# PT8211_T3_0_2.net
KiCad netlist of a schematic drawn in EAGLE
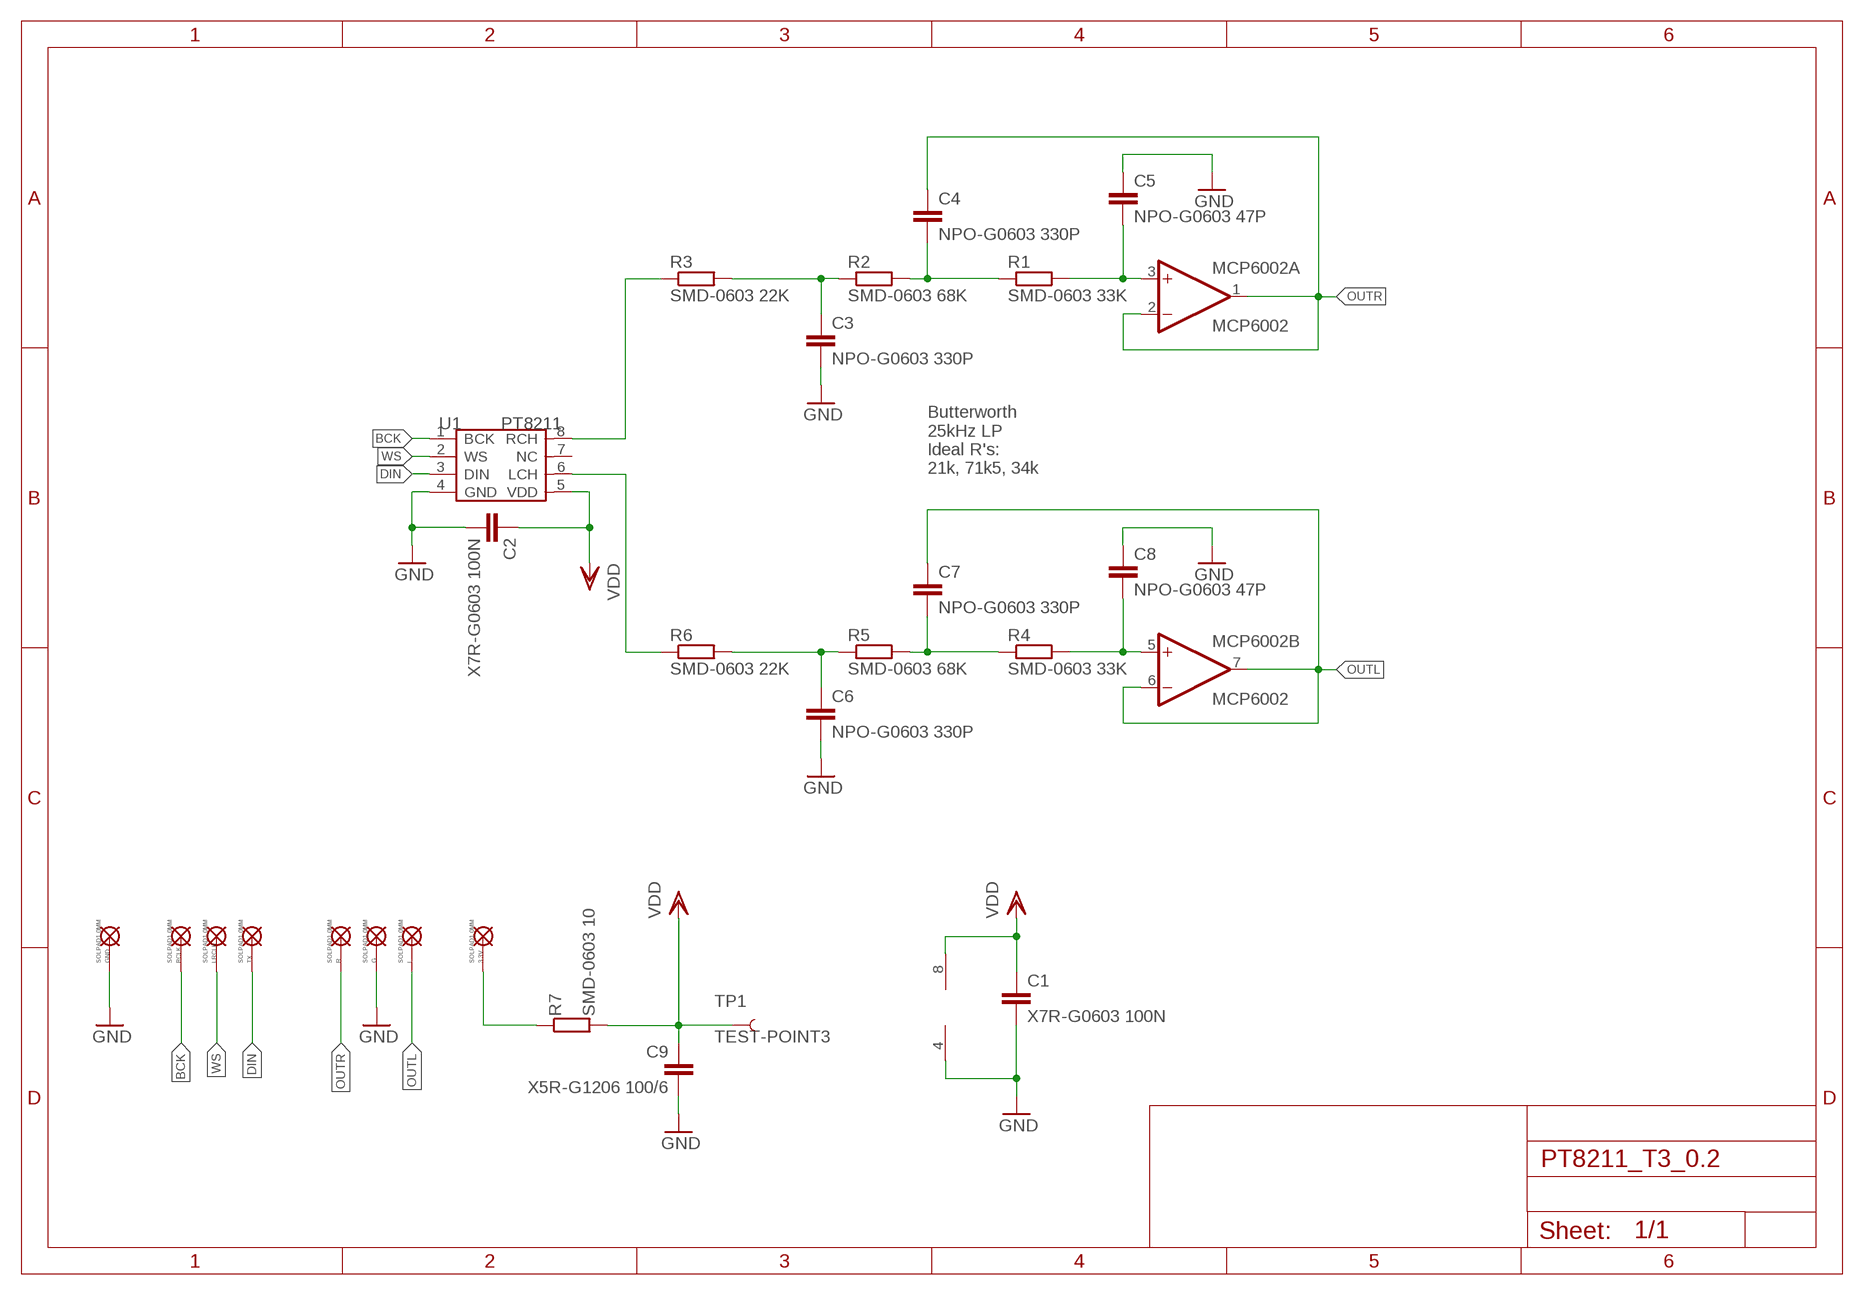
[diagram p0: schematic, sheet 1]

(export (version "E")
  (design (tool "Eeschema 10.0.6"))
  (components
    (comp (ref "3.3V")
      (value "SOLPAD1,0MM")
      (footprint "eagle-import:SOLPAD1MM")
      (libsource (lib "eagle-import") (part "SOLPAD1,0MM"))
    )
    (comp (ref "BCLK")
      (value "SOLPAD1,0MM")
      (footprint "eagle-import:SOLPAD1MM")
      (libsource (lib "eagle-import") (part "SOLPAD1,0MM"))
    )
    (comp (ref "C1")
      (value "X7R-G0603 100N")
      (footprint "eagle-import:C0603K")
      (libsource (lib "eagle-import") (part "C-EUC0603K"))
    )
    (comp (ref "C2")
      (value "X7R-G0603 100N")
      (footprint "eagle-import:C0603K")
      (libsource (lib "eagle-import") (part "C-EUC0603K"))
    )
    (comp (ref "C3")
      (value "NPO-G0603 330P")
      (footprint "eagle-import:C0603K")
      (libsource (lib "eagle-import") (part "C-EUC0603K"))
    )
    (comp (ref "C4")
      (value "NPO-G0603 330P")
      (footprint "eagle-import:C0603K")
      (libsource (lib "eagle-import") (part "C-EUC0603K"))
    )
    (comp (ref "C5")
      (value "NPO-G0603 47P")
      (footprint "eagle-import:C0603K")
      (libsource (lib "eagle-import") (part "C-EUC0603K"))
    )
    (comp (ref "C6")
      (value "NPO-G0603 330P")
      (footprint "eagle-import:C0603K")
      (libsource (lib "eagle-import") (part "C-EUC0603K"))
    )
    (comp (ref "C7")
      (value "NPO-G0603 330P")
      (footprint "eagle-import:C0603K")
      (libsource (lib "eagle-import") (part "C-EUC0603K"))
    )
    (comp (ref "C8")
      (value "NPO-G0603 47P")
      (footprint "eagle-import:C0603K")
      (libsource (lib "eagle-import") (part "C-EUC0603K"))
    )
    (comp (ref "C9")
      (value "X5R-G1206 100/6")
      (footprint "eagle-import:C1206K")
      (libsource (lib "eagle-import") (part "C-EUC1206K"))
    )
    (comp (ref "G")
      (value "SOLPAD1,0MM")
      (footprint "eagle-import:SOLPAD1MM")
      (libsource (lib "eagle-import") (part "SOLPAD1,0MM"))
    )
    (comp (ref "GND")
      (value "SOLPAD1,0MM")
      (footprint "eagle-import:SOLPAD1MM")
      (libsource (lib "eagle-import") (part "SOLPAD1,0MM"))
    )
    (comp (ref "L")
      (value "SOLPAD1,0MM")
      (footprint "eagle-import:SOLPAD1MM")
      (libsource (lib "eagle-import") (part "SOLPAD1,0MM"))
    )
    (comp (ref "LRCLK")
      (value "SOLPAD1,0MM")
      (footprint "eagle-import:SOLPAD1MM")
      (libsource (lib "eagle-import") (part "SOLPAD1,0MM"))
    )
    (comp (ref "MCP6002")
      (value "MCP6002")
      (footprint "eagle-import:SO08")
      (libsource (lib "eagle-import") (part "MCP602SN"))
    )
    (comp (ref "R")
      (value "SOLPAD1,0MM")
      (footprint "eagle-import:SOLPAD1MM")
      (libsource (lib "eagle-import") (part "SOLPAD1,0MM"))
    )
    (comp (ref "R1")
      (value "SMD-0603 33K")
      (footprint "eagle-import:R0603")
      (libsource (lib "eagle-import") (part "R-EU_R0603"))
    )
    (comp (ref "R2")
      (value "SMD-0603 68K")
      (footprint "eagle-import:R0603")
      (libsource (lib "eagle-import") (part "R-EU_R0603"))
    )
    (comp (ref "R3")
      (value "SMD-0603 22K")
      (footprint "eagle-import:R0603")
      (libsource (lib "eagle-import") (part "R-EU_R0603"))
    )
    (comp (ref "R4")
      (value "SMD-0603 33K")
      (footprint "eagle-import:R0603")
      (libsource (lib "eagle-import") (part "R-EU_R0603"))
    )
    (comp (ref "R5")
      (value "SMD-0603 68K")
      (footprint "eagle-import:R0603")
      (libsource (lib "eagle-import") (part "R-EU_R0603"))
    )
    (comp (ref "R6")
      (value "SMD-0603 22K")
      (footprint "eagle-import:R0603")
      (libsource (lib "eagle-import") (part "R-EU_R0603"))
    )
    (comp (ref "R7")
      (value "SMD-0603 10")
      (footprint "eagle-import:R0603")
      (libsource (lib "eagle-import") (part "R-EU_R0603"))
    )
    (comp (ref "TP1")
      (value "TEST-POINT3")
      (footprint "eagle-import:PAD.03X.03")
      (libsource (lib "eagle-import") (part "TEST-POINT3"))
    )
    (comp (ref "TX")
      (value "SOLPAD1,0MM")
      (footprint "eagle-import:SOLPAD1MM")
      (libsource (lib "eagle-import") (part "SOLPAD1,0MM"))
    )
    (comp (ref "U1")
      (value "PT8211")
      (footprint "eagle-import:SOP8-6.0-4.9X3.9")
      (libsource (lib "eagle-import") (part "PT8211-SOP8"))
    )
  )
  (nets
    (net (code "1") (name "BCK") (class "Default")
      (node (ref "BCLK") (pin "P$1") (pinfunction "P$1_P$1") (pintype "bidirectional"))
      (node (ref "U1") (pin "1") (pinfunction "BCK_1") (pintype "input"))
    )
    (net (code "2") (name "DIN") (class "Default")
      (node (ref "TX") (pin "P$1") (pinfunction "P$1_P$1") (pintype "bidirectional"))
      (node (ref "U1") (pin "3") (pinfunction "DIN_3") (pintype "input"))
    )
    (net (code "3") (name "GND") (class "Default")
      (node (ref "C1") (pin "2") (pinfunction "2_2") (pintype "passive"))
      (node (ref "C2") (pin "2") (pinfunction "2_2") (pintype "passive"))
      (node (ref "C3") (pin "2") (pinfunction "2_2") (pintype "passive"))
      (node (ref "C5") (pin "1") (pinfunction "1_1") (pintype "passive"))
      (node (ref "C6") (pin "2") (pinfunction "2_2") (pintype "passive"))
      (node (ref "C8") (pin "1") (pinfunction "1_1") (pintype "passive"))
      (node (ref "C9") (pin "2") (pinfunction "2_2") (pintype "passive"))
      (node (ref "G") (pin "P$1") (pinfunction "P$1_P$1") (pintype "bidirectional"))
      (node (ref "GND") (pin "P$1") (pinfunction "P$1_P$1") (pintype "bidirectional"))
      (node (ref "MCP6002") (pin "4") (pinfunction "V-_4") (pintype "power_in"))
      (node (ref "U1") (pin "4") (pinfunction "GND_4") (pintype "power_in"))
    )
    (net (code "4") (name "Net-(3.3V-PadP$1)") (class "Default")
      (node (ref "3.3V") (pin "P$1") (pinfunction "P$1_P$1") (pintype "bidirectional"))
      (node (ref "R7") (pin "1") (pinfunction "1_1") (pintype "passive"))
    )
    (net (code "5") (name "Net-(C3-Pad1)") (class "Default")
      (node (ref "C3") (pin "1") (pinfunction "1_1") (pintype "passive"))
      (node (ref "R2") (pin "1") (pinfunction "1_1") (pintype "passive"))
      (node (ref "R3") (pin "2") (pinfunction "2_2") (pintype "passive"))
    )
    (net (code "6") (name "Net-(C4-Pad2)") (class "Default")
      (node (ref "C4") (pin "2") (pinfunction "2_2") (pintype "passive"))
      (node (ref "R1") (pin "1") (pinfunction "1_1") (pintype "passive"))
      (node (ref "R2") (pin "2") (pinfunction "2_2") (pintype "passive"))
    )
    (net (code "7") (name "Net-(C6-Pad1)") (class "Default")
      (node (ref "C6") (pin "1") (pinfunction "1_1") (pintype "passive"))
      (node (ref "R5") (pin "1") (pinfunction "1_1") (pintype "passive"))
      (node (ref "R6") (pin "2") (pinfunction "2_2") (pintype "passive"))
    )
    (net (code "8") (name "Net-(C7-Pad2)") (class "Default")
      (node (ref "C7") (pin "2") (pinfunction "2_2") (pintype "passive"))
      (node (ref "R4") (pin "1") (pinfunction "1_1") (pintype "passive"))
      (node (ref "R5") (pin "2") (pinfunction "2_2") (pintype "passive"))
    )
    (net (code "9") (name "Net-(MCP6002A-+IN)") (class "Default")
      (node (ref "C5") (pin "2") (pinfunction "2_2") (pintype "passive"))
      (node (ref "MCP6002") (pin "3") (pinfunction "+IN_3") (pintype "input"))
      (node (ref "R1") (pin "2") (pinfunction "2_2") (pintype "passive"))
    )
    (net (code "10") (name "Net-(MCP6002B-+IN)") (class "Default")
      (node (ref "C8") (pin "2") (pinfunction "2_2") (pintype "passive"))
      (node (ref "MCP6002") (pin "5") (pinfunction "+IN_5") (pintype "input"))
      (node (ref "R4") (pin "2") (pinfunction "2_2") (pintype "passive"))
    )
    (net (code "11") (name "Net-(U1-LCH)") (class "Default")
      (node (ref "R6") (pin "1") (pinfunction "1_1") (pintype "passive"))
      (node (ref "U1") (pin "6") (pinfunction "LCH_6") (pintype "output"))
    )
    (net (code "12") (name "Net-(U1-RCH)") (class "Default")
      (node (ref "R3") (pin "1") (pinfunction "1_1") (pintype "passive"))
      (node (ref "U1") (pin "8") (pinfunction "RCH_8") (pintype "output"))
    )
    (net (code "13") (name "OUTL") (class "Default")
      (node (ref "C7") (pin "1") (pinfunction "1_1") (pintype "passive"))
      (node (ref "L") (pin "P$1") (pinfunction "P$1_P$1") (pintype "bidirectional"))
      (node (ref "MCP6002") (pin "6") (pinfunction "-IN_6") (pintype "input"))
      (node (ref "MCP6002") (pin "7") (pinfunction "OUT_7") (pintype "output"))
    )
    (net (code "14") (name "OUTR") (class "Default")
      (node (ref "C4") (pin "1") (pinfunction "1_1") (pintype "passive"))
      (node (ref "MCP6002") (pin "1") (pinfunction "OUT_1") (pintype "output"))
      (node (ref "MCP6002") (pin "2") (pinfunction "-IN_2") (pintype "input"))
      (node (ref "R") (pin "P$1") (pinfunction "P$1_P$1") (pintype "bidirectional"))
    )
    (net (code "15") (name "VDD") (class "Default")
      (node (ref "C1") (pin "1") (pinfunction "1_1") (pintype "passive"))
      (node (ref "C2") (pin "1") (pinfunction "1_1") (pintype "passive"))
      (node (ref "C9") (pin "1") (pinfunction "1_1") (pintype "passive"))
      (node (ref "MCP6002") (pin "8") (pinfunction "V+_8") (pintype "power_in"))
      (node (ref "R7") (pin "2") (pinfunction "2_2") (pintype "passive"))
      (node (ref "TP1") (pin "P$1") (pinfunction "1_P$1") (pintype "bidirectional"))
      (node (ref "U1") (pin "5") (pinfunction "VDD_5") (pintype "power_in"))
    )
    (net (code "16") (name "WS") (class "Default")
      (node (ref "LRCLK") (pin "P$1") (pinfunction "P$1_P$1") (pintype "bidirectional"))
      (node (ref "U1") (pin "2") (pinfunction "WS_2") (pintype "input"))
    )
    (net (code "17") (name "unconnected-(U1-NC-Pad7)") (class "Default")
      (node (ref "U1") (pin "7") (pinfunction "NC_7") (pintype "no_connect"))
    )
  )
)
